# carrier_card.net
KiCad netlist of a schematic drawn in Altium Designer
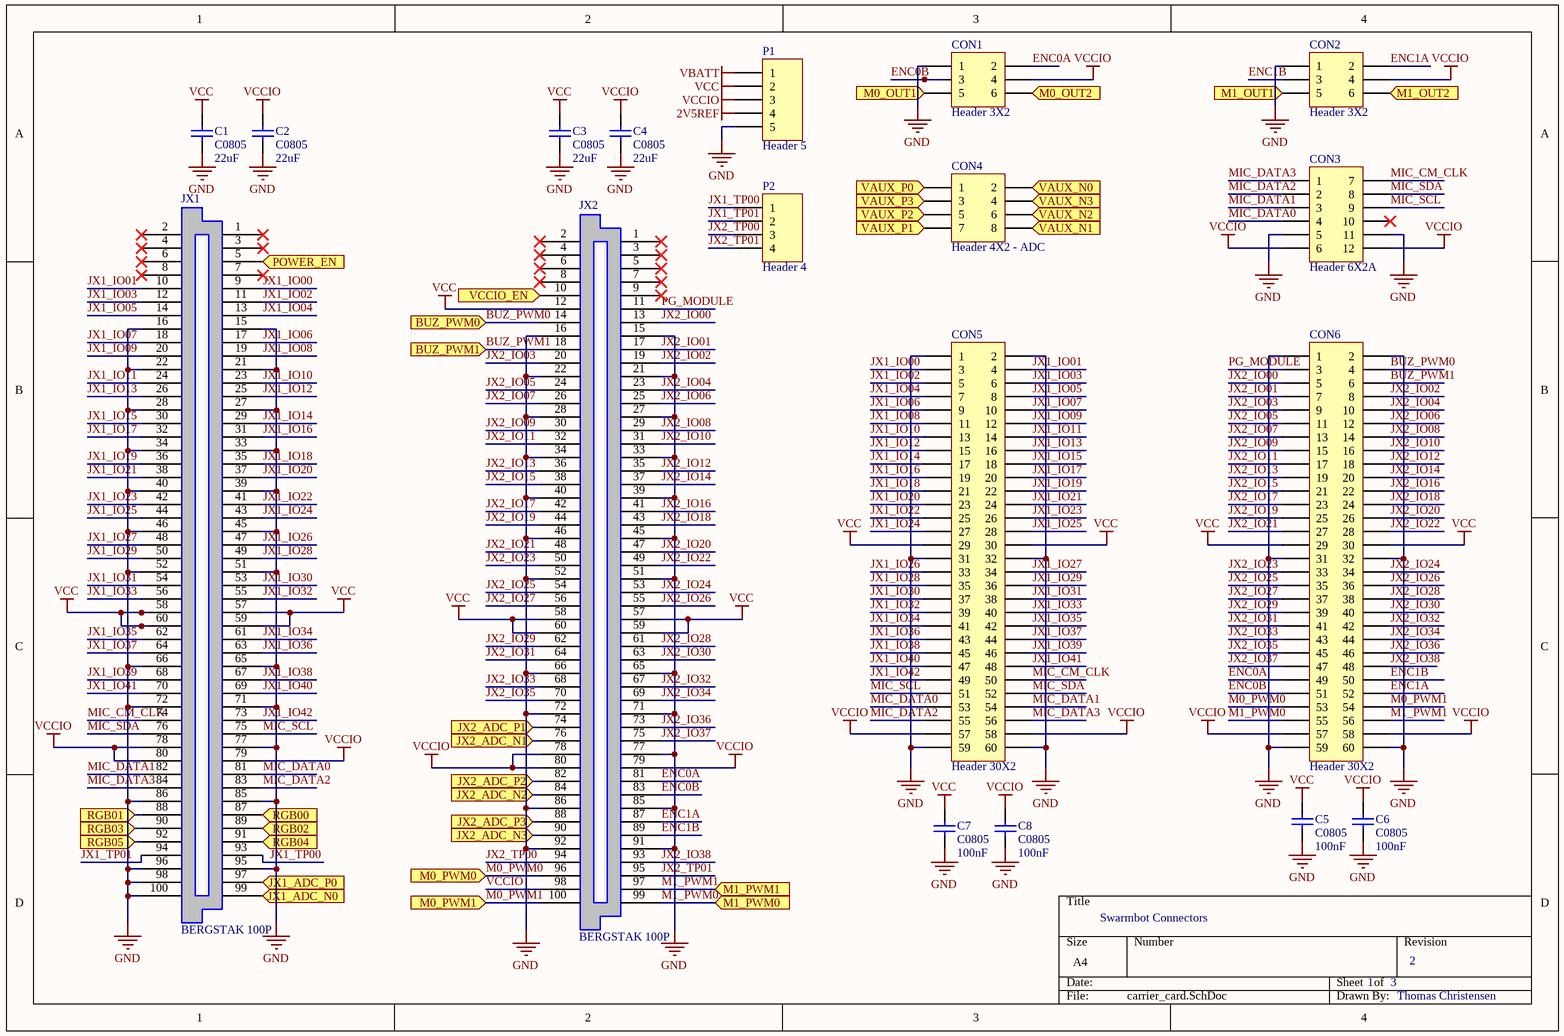
[diagram p0: carrier_card.SchDoc]

(export (version "E")
  (design (tool "Eeschema 10.0.6"))
  (components
    (comp (ref "C1")
      (value "C0805")
      (footprint "0805")
      (description "Ceramic Chip Capacitor - Standard")
      (fields (field (name "ALTIUM_VALUE") "22uF") (field (name "PUBLISHER") "Altium Limited"))
      (libsource (lib "KEMET Chip Capacitor") (part "C0805"))
    )
    (comp (ref "C2")
      (value "C0805")
      (footprint "0805")
      (description "Ceramic Chip Capacitor - Standard")
      (fields (field (name "ALTIUM_VALUE") "22uF") (field (name "PUBLISHER") "Altium Limited"))
      (libsource (lib "KEMET Chip Capacitor") (part "C0805"))
    )
    (comp (ref "C3")
      (value "C0805")
      (footprint "0805")
      (description "Ceramic Chip Capacitor - Standard")
      (fields (field (name "ALTIUM_VALUE") "22uF") (field (name "PUBLISHER") "Altium Limited"))
      (libsource (lib "KEMET Chip Capacitor") (part "C0805"))
    )
    (comp (ref "C4")
      (value "C0805")
      (footprint "0805")
      (description "Ceramic Chip Capacitor - Standard")
      (fields (field (name "ALTIUM_VALUE") "22uF") (field (name "PUBLISHER") "Altium Limited"))
      (libsource (lib "KEMET Chip Capacitor") (part "C0805"))
    )
    (comp (ref "C5")
      (value "C0805")
      (footprint "0805")
      (description "Ceramic Chip Capacitor - Standard")
      (fields (field (name "ALTIUM_VALUE") "100nF") (field (name "PUBLISHER") "Altium Limited"))
      (libsource (lib "KEMET Chip Capacitor") (part "C0805"))
    )
    (comp (ref "C6")
      (value "C0805")
      (footprint "0805")
      (description "Ceramic Chip Capacitor - Standard")
      (fields (field (name "ALTIUM_VALUE") "100nF") (field (name "PUBLISHER") "Altium Limited"))
      (libsource (lib "KEMET Chip Capacitor") (part "C0805"))
    )
    (comp (ref "C7")
      (value "C0805")
      (footprint "0805")
      (description "Ceramic Chip Capacitor - Standard")
      (fields (field (name "ALTIUM_VALUE") "100nF") (field (name "PUBLISHER") "Altium Limited"))
      (libsource (lib "KEMET Chip Capacitor") (part "C0805"))
    )
    (comp (ref "C8")
      (value "C0805")
      (footprint "0805")
      (description "Ceramic Chip Capacitor - Standard")
      (fields (field (name "ALTIUM_VALUE") "100nF") (field (name "PUBLISHER") "Altium Limited"))
      (libsource (lib "KEMET Chip Capacitor") (part "C0805"))
    )
    (comp (ref "CON1")
      (value "Header 3X2")
      (footprint "HDR2X3")
      (description "Header, 3-Pin, Dual row")
      (fields (field (name "PUBLISHER") "Altium Limited"))
      (libsource (lib "Miscellaneous Connectors") (part "Header 3X2"))
    )
    (comp (ref "CON2")
      (value "Header 3X2")
      (footprint "HDR2X3")
      (description "Header, 3-Pin, Dual row")
      (fields (field (name "PUBLISHER") "Altium Limited"))
      (libsource (lib "Miscellaneous Connectors") (part "Header 3X2"))
    )
    (comp (ref "CON3")
      (value "Header 6X2A")
      (footprint "HDR2X6_CEN")
      (description "Header, 6-Pin, Dual row")
      (fields (field (name "PUBLISHER") "Altium Limited"))
      (libsource (lib "Miscellaneous Connectors") (part "Header 6X2A"))
    )
    (comp (ref "CON4")
      (value "Header 4X2 - ADC")
      (footprint "HDR2X4")
      (description "Header, 4-Pin, Dual row")
      (fields (field (name "PUBLISHER") "Altium Limited"))
      (libsource (lib "Miscellaneous Connectors") (part "Header 4X2"))
    )
    (comp (ref "CON5")
      (value "Header 30X2")
      (footprint "HDR2X30")
      (description "Header, 30-Pin, Dual row")
      (fields (field (name "PUBLISHER") "Altium Limited"))
      (libsource (lib "Miscellaneous Connectors") (part "Header 30X2"))
    )
    (comp (ref "CON6")
      (value "Header 30X2")
      (footprint "HDR2X30")
      (description "Header, 30-Pin, Dual row")
      (fields (field (name "PUBLISHER") "Altium Limited"))
      (libsource (lib "Miscellaneous Connectors") (part "Header 30X2"))
    )
    (comp (ref "JX1")
      (value "BERGSTAK 100P")
      (footprint "swarmbot_pcblib:FCI_BERGSTAK_100P")
      (description "100p connector, BERGSTAK")
      (libsource (lib "swarmbot_schematic_library") (part "BERGSTAK 100P"))
    )
    (comp (ref "JX2")
      (value "BERGSTAK 100P")
      (footprint "swarmbot_pcblib:FCI_BERGSTAK_100P")
      (description "100p connector, BERGSTAK")
      (libsource (lib "swarmbot_schematic_library") (part "BERGSTAK 100P"))
    )
    (comp (ref "P1")
      (value "Header 5")
      (footprint "HDR1X5")
      (description "Header, 5-Pin")
      (fields (field (name "PUBLISHER") "Altium Limited"))
      (libsource (lib "Miscellaneous Connectors") (part "Header 5"))
    )
    (comp (ref "P2")
      (value "Header 4")
      (footprint "HDR1X4")
      (description "Header, 4-Pin")
      (fields (field (name "PUBLISHER") "Altium Limited"))
      (libsource (lib "Miscellaneous Connectors") (part "Header 4"))
    )
  )
  (nets
    (net (code "1") (name "/BUZ_PWM0") (class "Default")
      (node (ref "CON6") (pin "4") (pinfunction "4_4") (pintype "passive"))
      (node (ref "JX2") (pin "14") (pinfunction "14_14") (pintype "passive"))
    )
    (net (code "2") (name "/BUZ_PWM1") (class "Default")
      (node (ref "CON6") (pin "6") (pinfunction "6_6") (pintype "passive"))
      (node (ref "JX2") (pin "18") (pinfunction "18_18") (pintype "passive"))
    )
    (net (code "3") (name "/ENC0A") (class "Default")
      (node (ref "CON1") (pin "2") (pinfunction "2_2") (pintype "passive"))
      (node (ref "CON6") (pin "49") (pinfunction "49_49") (pintype "passive"))
      (node (ref "JX2") (pin "81") (pinfunction "81_81") (pintype "passive"))
    )
    (net (code "4") (name "/ENC0B") (class "Default")
      (node (ref "CON1") (pin "3") (pinfunction "3_3") (pintype "passive"))
      (node (ref "CON6") (pin "51") (pinfunction "51_51") (pintype "passive"))
      (node (ref "JX2") (pin "83") (pinfunction "83_83") (pintype "passive"))
    )
    (net (code "5") (name "/ENC1A") (class "Default")
      (node (ref "CON2") (pin "2") (pinfunction "2_2") (pintype "passive"))
      (node (ref "CON6") (pin "52") (pinfunction "52_52") (pintype "passive"))
      (node (ref "JX2") (pin "87") (pinfunction "87_87") (pintype "passive"))
    )
    (net (code "6") (name "/ENC1B") (class "Default")
      (node (ref "CON2") (pin "3") (pinfunction "3_3") (pintype "passive"))
      (node (ref "CON6") (pin "50") (pinfunction "50_50") (pintype "passive"))
      (node (ref "JX2") (pin "89") (pinfunction "89_89") (pintype "passive"))
    )
    (net (code "7") (name "/JX1_ADC_N0") (class "Default")
      (node (ref "JX1") (pin "99") (pinfunction "99_99") (pintype "passive"))
    )
    (net (code "8") (name "/JX1_ADC_P0") (class "Default")
      (node (ref "JX1") (pin "97") (pinfunction "97_97") (pintype "passive"))
    )
    (net (code "9") (name "/JX1_IO00") (class "Default")
      (node (ref "CON5") (pin "3") (pinfunction "3_3") (pintype "passive"))
      (node (ref "JX1") (pin "9") (pinfunction "9_9") (pintype "passive"))
    )
    (net (code "10") (name "/JX1_IO01") (class "Default")
      (node (ref "CON5") (pin "4") (pinfunction "4_4") (pintype "passive"))
      (node (ref "JX1") (pin "10") (pinfunction "10_10") (pintype "passive"))
    )
    (net (code "11") (name "/JX1_IO02") (class "Default")
      (node (ref "CON5") (pin "5") (pinfunction "5_5") (pintype "passive"))
      (node (ref "JX1") (pin "11") (pinfunction "11_11") (pintype "passive"))
    )
    (net (code "12") (name "/JX1_IO03") (class "Default")
      (node (ref "CON5") (pin "6") (pinfunction "6_6") (pintype "passive"))
      (node (ref "JX1") (pin "12") (pinfunction "12_12") (pintype "passive"))
    )
    (net (code "13") (name "/JX1_IO04") (class "Default")
      (node (ref "CON5") (pin "7") (pinfunction "7_7") (pintype "passive"))
      (node (ref "JX1") (pin "13") (pinfunction "13_13") (pintype "passive"))
    )
    (net (code "14") (name "/JX1_IO05") (class "Default")
      (node (ref "CON5") (pin "8") (pinfunction "8_8") (pintype "passive"))
      (node (ref "JX1") (pin "14") (pinfunction "14_14") (pintype "passive"))
    )
    (net (code "15") (name "/JX1_IO06") (class "Default")
      (node (ref "CON5") (pin "9") (pinfunction "9_9") (pintype "passive"))
      (node (ref "JX1") (pin "17") (pinfunction "17_17") (pintype "passive"))
    )
    (net (code "16") (name "/JX1_IO07") (class "Default")
      (node (ref "CON5") (pin "10") (pinfunction "10_10") (pintype "passive"))
      (node (ref "JX1") (pin "18") (pinfunction "18_18") (pintype "passive"))
    )
    (net (code "17") (name "/JX1_IO08") (class "Default")
      (node (ref "CON5") (pin "11") (pinfunction "11_11") (pintype "passive"))
      (node (ref "JX1") (pin "19") (pinfunction "19_19") (pintype "passive"))
    )
    (net (code "18") (name "/JX1_IO09") (class "Default")
      (node (ref "CON5") (pin "12") (pinfunction "12_12") (pintype "passive"))
      (node (ref "JX1") (pin "20") (pinfunction "20_20") (pintype "passive"))
    )
    (net (code "19") (name "/JX1_IO10") (class "Default")
      (node (ref "CON5") (pin "13") (pinfunction "13_13") (pintype "passive"))
      (node (ref "JX1") (pin "23") (pinfunction "23_23") (pintype "passive"))
    )
    (net (code "20") (name "/JX1_IO11") (class "Default")
      (node (ref "CON5") (pin "14") (pinfunction "14_14") (pintype "passive"))
      (node (ref "JX1") (pin "24") (pinfunction "24_24") (pintype "passive"))
    )
    (net (code "21") (name "/JX1_IO12") (class "Default")
      (node (ref "CON5") (pin "15") (pinfunction "15_15") (pintype "passive"))
      (node (ref "JX1") (pin "25") (pinfunction "25_25") (pintype "passive"))
    )
    (net (code "22") (name "/JX1_IO13") (class "Default")
      (node (ref "CON5") (pin "16") (pinfunction "16_16") (pintype "passive"))
      (node (ref "JX1") (pin "26") (pinfunction "26_26") (pintype "passive"))
    )
    (net (code "23") (name "/JX1_IO14") (class "Default")
      (node (ref "CON5") (pin "17") (pinfunction "17_17") (pintype "passive"))
      (node (ref "JX1") (pin "29") (pinfunction "29_29") (pintype "passive"))
    )
    (net (code "24") (name "/JX1_IO15") (class "Default")
      (node (ref "CON5") (pin "18") (pinfunction "18_18") (pintype "passive"))
      (node (ref "JX1") (pin "30") (pinfunction "30_30") (pintype "passive"))
    )
    (net (code "25") (name "/JX1_IO16") (class "Default")
      (node (ref "CON5") (pin "19") (pinfunction "19_19") (pintype "passive"))
      (node (ref "JX1") (pin "31") (pinfunction "31_31") (pintype "passive"))
    )
    (net (code "26") (name "/JX1_IO17") (class "Default")
      (node (ref "CON5") (pin "20") (pinfunction "20_20") (pintype "passive"))
      (node (ref "JX1") (pin "32") (pinfunction "32_32") (pintype "passive"))
    )
    (net (code "27") (name "/JX1_IO18") (class "Default")
      (node (ref "CON5") (pin "21") (pinfunction "21_21") (pintype "passive"))
      (node (ref "JX1") (pin "35") (pinfunction "35_35") (pintype "passive"))
    )
    (net (code "28") (name "/JX1_IO19") (class "Default")
      (node (ref "CON5") (pin "22") (pinfunction "22_22") (pintype "passive"))
      (node (ref "JX1") (pin "36") (pinfunction "36_36") (pintype "passive"))
    )
    (net (code "29") (name "/JX1_IO20") (class "Default")
      (node (ref "CON5") (pin "23") (pinfunction "23_23") (pintype "passive"))
      (node (ref "JX1") (pin "37") (pinfunction "37_37") (pintype "passive"))
    )
    (net (code "30") (name "/JX1_IO21") (class "Default")
      (node (ref "CON5") (pin "24") (pinfunction "24_24") (pintype "passive"))
      (node (ref "JX1") (pin "38") (pinfunction "38_38") (pintype "passive"))
    )
    (net (code "31") (name "/JX1_IO22") (class "Default")
      (node (ref "CON5") (pin "25") (pinfunction "25_25") (pintype "passive"))
      (node (ref "JX1") (pin "41") (pinfunction "41_41") (pintype "passive"))
    )
    (net (code "32") (name "/JX1_IO23") (class "Default")
      (node (ref "CON5") (pin "26") (pinfunction "26_26") (pintype "passive"))
      (node (ref "JX1") (pin "42") (pinfunction "42_42") (pintype "passive"))
    )
    (net (code "33") (name "/JX1_IO24") (class "Default")
      (node (ref "CON5") (pin "27") (pinfunction "27_27") (pintype "passive"))
      (node (ref "JX1") (pin "43") (pinfunction "43_43") (pintype "passive"))
    )
    (net (code "34") (name "/JX1_IO25") (class "Default")
      (node (ref "CON5") (pin "28") (pinfunction "28_28") (pintype "passive"))
      (node (ref "JX1") (pin "44") (pinfunction "44_44") (pintype "passive"))
    )
    (net (code "35") (name "/JX1_IO26") (class "Default")
      (node (ref "CON5") (pin "33") (pinfunction "33_33") (pintype "passive"))
      (node (ref "JX1") (pin "47") (pinfunction "47_47") (pintype "passive"))
    )
    (net (code "36") (name "/JX1_IO27") (class "Default")
      (node (ref "CON5") (pin "34") (pinfunction "34_34") (pintype "passive"))
      (node (ref "JX1") (pin "48") (pinfunction "48_48") (pintype "passive"))
    )
    (net (code "37") (name "/JX1_IO28") (class "Default")
      (node (ref "CON5") (pin "35") (pinfunction "35_35") (pintype "passive"))
      (node (ref "JX1") (pin "49") (pinfunction "49_49") (pintype "passive"))
    )
    (net (code "38") (name "/JX1_IO29") (class "Default")
      (node (ref "CON5") (pin "36") (pinfunction "36_36") (pintype "passive"))
      (node (ref "JX1") (pin "50") (pinfunction "50_50") (pintype "passive"))
    )
    (net (code "39") (name "/JX1_IO30") (class "Default")
      (node (ref "CON5") (pin "37") (pinfunction "37_37") (pintype "passive"))
      (node (ref "JX1") (pin "53") (pinfunction "53_53") (pintype "passive"))
    )
    (net (code "40") (name "/JX1_IO31") (class "Default")
      (node (ref "CON5") (pin "38") (pinfunction "38_38") (pintype "passive"))
      (node (ref "JX1") (pin "54") (pinfunction "54_54") (pintype "passive"))
    )
    (net (code "41") (name "/JX1_IO32") (class "Default")
      (node (ref "CON5") (pin "39") (pinfunction "39_39") (pintype "passive"))
      (node (ref "JX1") (pin "55") (pinfunction "55_55") (pintype "passive"))
    )
    (net (code "42") (name "/JX1_IO33") (class "Default")
      (node (ref "CON5") (pin "40") (pinfunction "40_40") (pintype "passive"))
      (node (ref "JX1") (pin "56") (pinfunction "56_56") (pintype "passive"))
    )
    (net (code "43") (name "/JX1_IO34") (class "Default")
      (node (ref "CON5") (pin "41") (pinfunction "41_41") (pintype "passive"))
      (node (ref "JX1") (pin "61") (pinfunction "61_61") (pintype "passive"))
    )
    (net (code "44") (name "/JX1_IO35") (class "Default")
      (node (ref "CON5") (pin "42") (pinfunction "42_42") (pintype "passive"))
      (node (ref "JX1") (pin "62") (pinfunction "62_62") (pintype "passive"))
    )
    (net (code "45") (name "/JX1_IO36") (class "Default")
      (node (ref "CON5") (pin "43") (pinfunction "43_43") (pintype "passive"))
      (node (ref "JX1") (pin "63") (pinfunction "63_63") (pintype "passive"))
    )
    (net (code "46") (name "/JX1_IO37") (class "Default")
      (node (ref "CON5") (pin "44") (pinfunction "44_44") (pintype "passive"))
      (node (ref "JX1") (pin "64") (pinfunction "64_64") (pintype "passive"))
    )
    (net (code "47") (name "/JX1_IO38") (class "Default")
      (node (ref "CON5") (pin "45") (pinfunction "45_45") (pintype "passive"))
      (node (ref "JX1") (pin "67") (pinfunction "67_67") (pintype "passive"))
    )
    (net (code "48") (name "/JX1_IO39") (class "Default")
      (node (ref "CON5") (pin "46") (pinfunction "46_46") (pintype "passive"))
      (node (ref "JX1") (pin "68") (pinfunction "68_68") (pintype "passive"))
    )
    (net (code "49") (name "/JX1_IO40") (class "Default")
      (node (ref "CON5") (pin "47") (pinfunction "47_47") (pintype "passive"))
      (node (ref "JX1") (pin "69") (pinfunction "69_69") (pintype "passive"))
    )
    (net (code "50") (name "/JX1_IO41") (class "Default")
      (node (ref "CON5") (pin "48") (pinfunction "48_48") (pintype "passive"))
      (node (ref "JX1") (pin "70") (pinfunction "70_70") (pintype "passive"))
    )
    (net (code "51") (name "/JX1_IO42") (class "Default")
      (node (ref "CON5") (pin "49") (pinfunction "49_49") (pintype "passive"))
      (node (ref "JX1") (pin "73") (pinfunction "73_73") (pintype "passive"))
    )
    (net (code "52") (name "/JX1_TP00") (class "Default")
      (node (ref "JX1") (pin "93") (pinfunction "93_93") (pintype "passive"))
      (node (ref "P2") (pin "1") (pinfunction "1_1") (pintype "passive"))
    )
    (net (code "53") (name "/JX1_TP01") (class "Default")
      (node (ref "JX1") (pin "94") (pinfunction "94_94") (pintype "passive"))
      (node (ref "P2") (pin "2") (pinfunction "2_2") (pintype "passive"))
    )
    (net (code "54") (name "/JX2_ADC_N1") (class "Default")
      (node (ref "JX2") (pin "76") (pinfunction "76_76") (pintype "passive"))
    )
    (net (code "55") (name "/JX2_ADC_N2") (class "Default")
      (node (ref "JX2") (pin "84") (pinfunction "84_84") (pintype "passive"))
    )
    (net (code "56") (name "/JX2_ADC_N3") (class "Default")
      (node (ref "JX2") (pin "90") (pinfunction "90_90") (pintype "passive"))
    )
    (net (code "57") (name "/JX2_ADC_P1") (class "Default")
      (node (ref "JX2") (pin "74") (pinfunction "74_74") (pintype "passive"))
    )
    (net (code "58") (name "/JX2_ADC_P2") (class "Default")
      (node (ref "JX2") (pin "82") (pinfunction "82_82") (pintype "passive"))
    )
    (net (code "59") (name "/JX2_ADC_P3") (class "Default")
      (node (ref "JX2") (pin "88") (pinfunction "88_88") (pintype "passive"))
    )
    (net (code "60") (name "/JX2_IO00") (class "Default")
      (node (ref "CON6") (pin "5") (pinfunction "5_5") (pintype "passive"))
      (node (ref "JX2") (pin "13") (pinfunction "13_13") (pintype "passive"))
    )
    (net (code "61") (name "/JX2_IO01") (class "Default")
      (node (ref "CON6") (pin "7") (pinfunction "7_7") (pintype "passive"))
      (node (ref "JX2") (pin "17") (pinfunction "17_17") (pintype "passive"))
    )
    (net (code "62") (name "/JX2_IO02") (class "Default")
      (node (ref "CON6") (pin "8") (pinfunction "8_8") (pintype "passive"))
      (node (ref "JX2") (pin "19") (pinfunction "19_19") (pintype "passive"))
    )
    (net (code "63") (name "/JX2_IO03") (class "Default")
      (node (ref "CON6") (pin "9") (pinfunction "9_9") (pintype "passive"))
      (node (ref "JX2") (pin "20") (pinfunction "20_20") (pintype "passive"))
    )
    (net (code "64") (name "/JX2_IO04") (class "Default")
      (node (ref "CON6") (pin "10") (pinfunction "10_10") (pintype "passive"))
      (node (ref "JX2") (pin "23") (pinfunction "23_23") (pintype "passive"))
    )
    (net (code "65") (name "/JX2_IO05") (class "Default")
      (node (ref "CON6") (pin "11") (pinfunction "11_11") (pintype "passive"))
      (node (ref "JX2") (pin "24") (pinfunction "24_24") (pintype "passive"))
    )
    (net (code "66") (name "/JX2_IO06") (class "Default")
      (node (ref "CON6") (pin "12") (pinfunction "12_12") (pintype "passive"))
      (node (ref "JX2") (pin "25") (pinfunction "25_25") (pintype "passive"))
    )
    (net (code "67") (name "/JX2_IO07") (class "Default")
      (node (ref "CON6") (pin "13") (pinfunction "13_13") (pintype "passive"))
      (node (ref "JX2") (pin "26") (pinfunction "26_26") (pintype "passive"))
    )
    (net (code "68") (name "/JX2_IO08") (class "Default")
      (node (ref "CON6") (pin "14") (pinfunction "14_14") (pintype "passive"))
      (node (ref "JX2") (pin "29") (pinfunction "29_29") (pintype "passive"))
    )
    (net (code "69") (name "/JX2_IO09") (class "Default")
      (node (ref "CON6") (pin "15") (pinfunction "15_15") (pintype "passive"))
      (node (ref "JX2") (pin "30") (pinfunction "30_30") (pintype "passive"))
    )
    (net (code "70") (name "/JX2_IO10") (class "Default")
      (node (ref "CON6") (pin "16") (pinfunction "16_16") (pintype "passive"))
      (node (ref "JX2") (pin "31") (pinfunction "31_31") (pintype "passive"))
    )
    (net (code "71") (name "/JX2_IO11") (class "Default")
      (node (ref "CON6") (pin "17") (pinfunction "17_17") (pintype "passive"))
      (node (ref "JX2") (pin "32") (pinfunction "32_32") (pintype "passive"))
    )
    (net (code "72") (name "/JX2_IO12") (class "Default")
      (node (ref "CON6") (pin "18") (pinfunction "18_18") (pintype "passive"))
      (node (ref "JX2") (pin "35") (pinfunction "35_35") (pintype "passive"))
    )
    (net (code "73") (name "/JX2_IO13") (class "Default")
      (node (ref "CON6") (pin "19") (pinfunction "19_19") (pintype "passive"))
      (node (ref "JX2") (pin "36") (pinfunction "36_36") (pintype "passive"))
    )
    (net (code "74") (name "/JX2_IO14") (class "Default")
      (node (ref "CON6") (pin "20") (pinfunction "20_20") (pintype "passive"))
      (node (ref "JX2") (pin "37") (pinfunction "37_37") (pintype "passive"))
    )
    (net (code "75") (name "/JX2_IO15") (class "Default")
      (node (ref "CON6") (pin "21") (pinfunction "21_21") (pintype "passive"))
      (node (ref "JX2") (pin "38") (pinfunction "38_38") (pintype "passive"))
    )
    (net (code "76") (name "/JX2_IO16") (class "Default")
      (node (ref "CON6") (pin "22") (pinfunction "22_22") (pintype "passive"))
      (node (ref "JX2") (pin "41") (pinfunction "41_41") (pintype "passive"))
    )
    (net (code "77") (name "/JX2_IO17") (class "Default")
      (node (ref "CON6") (pin "23") (pinfunction "23_23") (pintype "passive"))
      (node (ref "JX2") (pin "42") (pinfunction "42_42") (pintype "passive"))
    )
    (net (code "78") (name "/JX2_IO18") (class "Default")
      (node (ref "CON6") (pin "24") (pinfunction "24_24") (pintype "passive"))
      (node (ref "JX2") (pin "43") (pinfunction "43_43") (pintype "passive"))
    )
    (net (code "79") (name "/JX2_IO19") (class "Default")
      (node (ref "CON6") (pin "25") (pinfunction "25_25") (pintype "passive"))
      (node (ref "JX2") (pin "44") (pinfunction "44_44") (pintype "passive"))
    )
    (net (code "80") (name "/JX2_IO20") (class "Default")
      (node (ref "CON6") (pin "26") (pinfunction "26_26") (pintype "passive"))
      (node (ref "JX2") (pin "47") (pinfunction "47_47") (pintype "passive"))
    )
    (net (code "81") (name "/JX2_IO21") (class "Default")
      (node (ref "CON6") (pin "27") (pinfunction "27_27") (pintype "passive"))
      (node (ref "JX2") (pin "48") (pinfunction "48_48") (pintype "passive"))
    )
    (net (code "82") (name "/JX2_IO22") (class "Default")
      (node (ref "CON6") (pin "28") (pinfunction "28_28") (pintype "passive"))
      (node (ref "JX2") (pin "49") (pinfunction "49_49") (pintype "passive"))
    )
    (net (code "83") (name "/JX2_IO23") (class "Default")
      (node (ref "CON6") (pin "33") (pinfunction "33_33") (pintype "passive"))
      (node (ref "JX2") (pin "50") (pinfunction "50_50") (pintype "passive"))
    )
    (net (code "84") (name "/JX2_IO24") (class "Default")
      (node (ref "CON6") (pin "34") (pinfunction "34_34") (pintype "passive"))
      (node (ref "JX2") (pin "53") (pinfunction "53_53") (pintype "passive"))
    )
    (net (code "85") (name "/JX2_IO25") (class "Default")
      (node (ref "CON6") (pin "35") (pinfunction "35_35") (pintype "passive"))
      (node (ref "JX2") (pin "54") (pinfunction "54_54") (pintype "passive"))
    )
    (net (code "86") (name "/JX2_IO26") (class "Default")
      (node (ref "CON6") (pin "36") (pinfunction "36_36") (pintype "passive"))
      (node (ref "JX2") (pin "55") (pinfunction "55_55") (pintype "passive"))
    )
    (net (code "87") (name "/JX2_IO27") (class "Default")
      (node (ref "CON6") (pin "37") (pinfunction "37_37") (pintype "passive"))
      (node (ref "JX2") (pin "56") (pinfunction "56_56") (pintype "passive"))
    )
    (net (code "88") (name "/JX2_IO28") (class "Default")
      (node (ref "CON6") (pin "38") (pinfunction "38_38") (pintype "passive"))
      (node (ref "JX2") (pin "61") (pinfunction "61_61") (pintype "passive"))
    )
    (net (code "89") (name "/JX2_IO29") (class "Default")
      (node (ref "CON6") (pin "39") (pinfunction "39_39") (pintype "passive"))
      (node (ref "JX2") (pin "62") (pinfunction "62_62") (pintype "passive"))
    )
    (net (code "90") (name "/JX2_IO30") (class "Default")
      (node (ref "CON6") (pin "40") (pinfunction "40_40") (pintype "passive"))
      (node (ref "JX2") (pin "63") (pinfunction "63_63") (pintype "passive"))
    )
    (net (code "91") (name "/JX2_IO31") (class "Default")
      (node (ref "CON6") (pin "41") (pinfunction "41_41") (pintype "passive"))
      (node (ref "JX2") (pin "64") (pinfunction "64_64") (pintype "passive"))
    )
    (net (code "92") (name "/JX2_IO32") (class "Default")
      (node (ref "CON6") (pin "42") (pinfunction "42_42") (pintype "passive"))
      (node (ref "JX2") (pin "67") (pinfunction "67_67") (pintype "passive"))
    )
    (net (code "93") (name "/JX2_IO33") (class "Default")
      (node (ref "CON6") (pin "43") (pinfunction "43_43") (pintype "passive"))
      (node (ref "JX2") (pin "68") (pinfunction "68_68") (pintype "passive"))
    )
    (net (code "94") (name "/JX2_IO34") (class "Default")
      (node (ref "CON6") (pin "44") (pinfunction "44_44") (pintype "passive"))
      (node (ref "JX2") (pin "69") (pinfunction "69_69") (pintype "passive"))
    )
    (net (code "95") (name "/JX2_IO35") (class "Default")
      (node (ref "CON6") (pin "45") (pinfunction "45_45") (pintype "passive"))
      (node (ref "JX2") (pin "70") (pinfunction "70_70") (pintype "passive"))
    )
    (net (code "96") (name "/JX2_IO36") (class "Default")
      (node (ref "CON6") (pin "46") (pinfunction "46_46") (pintype "passive"))
      (node (ref "JX2") (pin "73") (pinfunction "73_73") (pintype "passive"))
    )
    (net (code "97") (name "/JX2_IO37") (class "Default")
      (node (ref "CON6") (pin "47") (pinfunction "47_47") (pintype "passive"))
      (node (ref "JX2") (pin "75") (pinfunction "75_75") (pintype "passive"))
    )
    (net (code "98") (name "/JX2_IO38") (class "Default")
      (node (ref "CON6") (pin "48") (pinfunction "48_48") (pintype "passive"))
      (node (ref "JX2") (pin "93") (pinfunction "93_93") (pintype "passive"))
    )
    (net (code "99") (name "/JX2_TP00") (class "Default")
      (node (ref "JX2") (pin "94") (pinfunction "94_94") (pintype "passive"))
      (node (ref "P2") (pin "3") (pinfunction "3_3") (pintype "passive"))
    )
    (net (code "100") (name "/JX2_TP01") (class "Default")
      (node (ref "JX2") (pin "95") (pinfunction "95_95") (pintype "passive"))
      (node (ref "P2") (pin "4") (pinfunction "4_4") (pintype "passive"))
    )
    (net (code "101") (name "/M0_OUT1") (class "Default")
      (node (ref "CON1") (pin "5") (pinfunction "5_5") (pintype "passive"))
    )
    (net (code "102") (name "/M0_OUT2") (class "Default")
      (node (ref "CON1") (pin "6") (pinfunction "6_6") (pintype "passive"))
    )
    (net (code "103") (name "/M0_PWM0") (class "Default")
      (node (ref "CON6") (pin "53") (pinfunction "53_53") (pintype "passive"))
      (node (ref "JX2") (pin "96") (pinfunction "96_96") (pintype "passive"))
    )
    (net (code "104") (name "/M0_PWM1") (class "Default")
      (node (ref "CON6") (pin "54") (pinfunction "54_54") (pintype "passive"))
      (node (ref "JX2") (pin "100") (pinfunction "100_100") (pintype "passive"))
    )
    (net (code "105") (name "/M1_OUT1") (class "Default")
      (node (ref "CON2") (pin "5") (pinfunction "5_5") (pintype "passive"))
    )
    (net (code "106") (name "/M1_OUT2") (class "Default")
      (node (ref "CON2") (pin "6") (pinfunction "6_6") (pintype "passive"))
    )
    (net (code "107") (name "/M1_PWM0") (class "Default")
      (node (ref "CON6") (pin "55") (pinfunction "55_55") (pintype "passive"))
      (node (ref "JX2") (pin "99") (pinfunction "99_99") (pintype "passive"))
    )
    (net (code "108") (name "/M1_PWM1") (class "Default")
      (node (ref "CON6") (pin "56") (pinfunction "56_56") (pintype "passive"))
      (node (ref "JX2") (pin "97") (pinfunction "97_97") (pintype "passive"))
    )
    (net (code "109") (name "/MIC_CM_CLK") (class "Default")
      (node (ref "CON3") (pin "7") (pinfunction "7_7") (pintype "passive"))
      (node (ref "CON5") (pin "50") (pinfunction "50_50") (pintype "passive"))
      (node (ref "JX1") (pin "74") (pinfunction "74_74") (pintype "passive"))
    )
    (net (code "110") (name "/MIC_DATA0") (class "Default")
      (node (ref "CON3") (pin "4") (pinfunction "4_4") (pintype "passive"))
      (node (ref "CON5") (pin "53") (pinfunction "53_53") (pintype "passive"))
      (node (ref "JX1") (pin "81") (pinfunction "81_81") (pintype "passive"))
    )
    (net (code "111") (name "/MIC_DATA1") (class "Default")
      (node (ref "CON3") (pin "3") (pinfunction "3_3") (pintype "passive"))
      (node (ref "CON5") (pin "54") (pinfunction "54_54") (pintype "passive"))
      (node (ref "JX1") (pin "82") (pinfunction "82_82") (pintype "passive"))
    )
    (net (code "112") (name "/MIC_DATA2") (class "Default")
      (node (ref "CON3") (pin "2") (pinfunction "2_2") (pintype "passive"))
      (node (ref "CON5") (pin "55") (pinfunction "55_55") (pintype "passive"))
      (node (ref "JX1") (pin "83") (pinfunction "83_83") (pintype "passive"))
    )
    (net (code "113") (name "/MIC_DATA3") (class "Default")
      (node (ref "CON3") (pin "1") (pinfunction "1_1") (pintype "passive"))
      (node (ref "CON5") (pin "56") (pinfunction "56_56") (pintype "passive"))
      (node (ref "JX1") (pin "84") (pinfunction "84_84") (pintype "passive"))
    )
    (net (code "114") (name "/MIC_SCL") (class "Default")
      (node (ref "CON3") (pin "9") (pinfunction "9_9") (pintype "passive"))
      (node (ref "CON5") (pin "51") (pinfunction "51_51") (pintype "passive"))
      (node (ref "JX1") (pin "75") (pinfunction "75_75") (pintype "passive"))
    )
    (net (code "115") (name "/MIC_SDA") (class "Default")
      (node (ref "CON3") (pin "8") (pinfunction "8_8") (pintype "passive"))
      (node (ref "CON5") (pin "52") (pinfunction "52_52") (pintype "passive"))
      (node (ref "JX1") (pin "76") (pinfunction "76_76") (pintype "passive"))
    )
    (net (code "116") (name "/PG_MODULE") (class "Default")
      (node (ref "CON6") (pin "3") (pinfunction "3_3") (pintype "passive"))
      (node (ref "JX2") (pin "11") (pinfunction "11_11") (pintype "passive"))
    )
    (net (code "117") (name "/POWER_EN") (class "Default")
      (node (ref "JX1") (pin "5") (pinfunction "5_5") (pintype "passive"))
    )
    (net (code "118") (name "/RGB00") (class "Default")
      (node (ref "JX1") (pin "87") (pinfunction "87_87") (pintype "passive"))
    )
    (net (code "119") (name "/RGB01") (class "Default")
      (node (ref "JX1") (pin "88") (pinfunction "88_88") (pintype "passive"))
    )
    (net (code "120") (name "/RGB02") (class "Default")
      (node (ref "JX1") (pin "89") (pinfunction "89_89") (pintype "passive"))
    )
    (net (code "121") (name "/RGB03") (class "Default")
      (node (ref "JX1") (pin "90") (pinfunction "90_90") (pintype "passive"))
    )
    (net (code "122") (name "/RGB04") (class "Default")
      (node (ref "JX1") (pin "91") (pinfunction "91_91") (pintype "passive"))
    )
    (net (code "123") (name "/RGB05") (class "Default")
      (node (ref "JX1") (pin "92") (pinfunction "92_92") (pintype "passive"))
    )
    (net (code "124") (name "/VAUX_N0") (class "Default")
      (node (ref "CON4") (pin "2") (pinfunction "2_2") (pintype "passive"))
    )
    (net (code "125") (name "/VAUX_N1") (class "Default")
      (node (ref "CON4") (pin "8") (pinfunction "8_8") (pintype "passive"))
    )
    (net (code "126") (name "/VAUX_N2") (class "Default")
      (node (ref "CON4") (pin "6") (pinfunction "6_6") (pintype "passive"))
    )
    (net (code "127") (name "/VAUX_N3") (class "Default")
      (node (ref "CON4") (pin "4") (pinfunction "4_4") (pintype "passive"))
    )
    (net (code "128") (name "/VAUX_P0") (class "Default")
      (node (ref "CON4") (pin "1") (pinfunction "1_1") (pintype "passive"))
    )
    (net (code "129") (name "/VAUX_P1") (class "Default")
      (node (ref "CON4") (pin "7") (pinfunction "7_7") (pintype "passive"))
    )
    (net (code "130") (name "/VAUX_P2") (class "Default")
      (node (ref "CON4") (pin "5") (pinfunction "5_5") (pintype "passive"))
    )
    (net (code "131") (name "/VAUX_P3") (class "Default")
      (node (ref "CON4") (pin "3") (pinfunction "3_3") (pintype "passive"))
    )
    (net (code "132") (name "/VCCIO_EN") (class "Default")
      (node (ref "JX2") (pin "10") (pinfunction "10_10") (pintype "passive"))
    )
    (net (code "133") (name "2V5REF") (class "Default")
      (node (ref "P1") (pin "4") (pinfunction "4_4") (pintype "passive"))
    )
    (net (code "134") (name "GND") (class "Default")
      (node (ref "C1") (pin "1") (pinfunction "1_1") (pintype "passive"))
      (node (ref "C2") (pin "1") (pinfunction "1_1") (pintype "passive"))
      (node (ref "C3") (pin "1") (pinfunction "1_1") (pintype "passive"))
      (node (ref "C4") (pin "1") (pinfunction "1_1") (pintype "passive"))
      (node (ref "C5") (pin "1") (pinfunction "1_1") (pintype "passive"))
      (node (ref "C6") (pin "1") (pinfunction "1_1") (pintype "passive"))
      (node (ref "C7") (pin "1") (pinfunction "1_1") (pintype "passive"))
      (node (ref "C8") (pin "1") (pinfunction "1_1") (pintype "passive"))
      (node (ref "CON1") (pin "1") (pinfunction "1_1") (pintype "passive"))
      (node (ref "CON2") (pin "1") (pinfunction "1_1") (pintype "passive"))
      (node (ref "CON3") (pin "11") (pinfunction "11_11") (pintype "passive"))
      (node (ref "CON3") (pin "5") (pinfunction "5_5") (pintype "passive"))
      (node (ref "CON5") (pin "1") (pinfunction "1_1") (pintype "passive"))
      (node (ref "CON5") (pin "2") (pinfunction "2_2") (pintype "passive"))
      (node (ref "CON5") (pin "31") (pinfunction "31_31") (pintype "passive"))
      (node (ref "CON5") (pin "32") (pinfunction "32_32") (pintype "passive"))
      (node (ref "CON5") (pin "59") (pinfunction "59_59") (pintype "passive"))
      (node (ref "CON5") (pin "60") (pinfunction "60_60") (pintype "passive"))
      (node (ref "CON6") (pin "1") (pinfunction "1_1") (pintype "passive"))
      (node (ref "CON6") (pin "2") (pinfunction "2_2") (pintype "passive"))
      (node (ref "CON6") (pin "31") (pinfunction "31_31") (pintype "passive"))
      (node (ref "CON6") (pin "32") (pinfunction "32_32") (pintype "passive"))
      (node (ref "CON6") (pin "59") (pinfunction "59_59") (pintype "passive"))
      (node (ref "CON6") (pin "60") (pinfunction "60_60") (pintype "passive"))
      (node (ref "JX1") (pin "100") (pinfunction "100_100") (pintype "passive"))
      (node (ref "JX1") (pin "15") (pinfunction "15_15") (pintype "passive"))
      (node (ref "JX1") (pin "16") (pinfunction "16_16") (pintype "passive"))
      (node (ref "JX1") (pin "21") (pinfunction "21_21") (pintype "passive"))
      (node (ref "JX1") (pin "22") (pinfunction "22_22") (pintype "passive"))
      (node (ref "JX1") (pin "27") (pinfunction "27_27") (pintype "passive"))
      (node (ref "JX1") (pin "28") (pinfunction "28_28") (pintype "passive"))
      (node (ref "JX1") (pin "33") (pinfunction "33_33") (pintype "passive"))
      (node (ref "JX1") (pin "34") (pinfunction "34_34") (pintype "passive"))
      (node (ref "JX1") (pin "39") (pinfunction "39_39") (pintype "passive"))
      (node (ref "JX1") (pin "40") (pinfunction "40_40") (pintype "passive"))
      (node (ref "JX1") (pin "45") (pinfunction "45_45") (pintype "passive"))
      (node (ref "JX1") (pin "46") (pinfunction "46_46") (pintype "passive"))
      (node (ref "JX1") (pin "51") (pinfunction "51_51") (pintype "passive"))
      (node (ref "JX1") (pin "52") (pinfunction "52_52") (pintype "passive"))
      (node (ref "JX1") (pin "65") (pinfunction "65_65") (pintype "passive"))
      (node (ref "JX1") (pin "66") (pinfunction "66_66") (pintype "passive"))
      (node (ref "JX1") (pin "71") (pinfunction "71_71") (pintype "passive"))
      (node (ref "JX1") (pin "72") (pinfunction "72_72") (pintype "passive"))
      (node (ref "JX1") (pin "77") (pinfunction "77_77") (pintype "passive"))
      (node (ref "JX1") (pin "85") (pinfunction "85_85") (pintype "passive"))
      (node (ref "JX1") (pin "86") (pinfunction "86_86") (pintype "passive"))
      (node (ref "JX1") (pin "95") (pinfunction "95_95") (pintype "passive"))
      (node (ref "JX1") (pin "96") (pinfunction "96_96") (pintype "passive"))
      (node (ref "JX1") (pin "98") (pinfunction "98_98") (pintype "passive"))
      (node (ref "JX2") (pin "15") (pinfunction "15_15") (pintype "passive"))
      (node (ref "JX2") (pin "16") (pinfunction "16_16") (pintype "passive"))
      (node (ref "JX2") (pin "21") (pinfunction "21_21") (pintype "passive"))
      (node (ref "JX2") (pin "22") (pinfunction "22_22") (pintype "passive"))
      (node (ref "JX2") (pin "27") (pinfunction "27_27") (pintype "passive"))
      (node (ref "JX2") (pin "28") (pinfunction "28_28") (pintype "passive"))
      (node (ref "JX2") (pin "33") (pinfunction "33_33") (pintype "passive"))
      (node (ref "JX2") (pin "34") (pinfunction "34_34") (pintype "passive"))
      (node (ref "JX2") (pin "39") (pinfunction "39_39") (pintype "passive"))
      (node (ref "JX2") (pin "40") (pinfunction "40_40") (pintype "passive"))
      (node (ref "JX2") (pin "45") (pinfunction "45_45") (pintype "passive"))
      (node (ref "JX2") (pin "46") (pinfunction "46_46") (pintype "passive"))
      (node (ref "JX2") (pin "51") (pinfunction "51_51") (pintype "passive"))
      (node (ref "JX2") (pin "52") (pinfunction "52_52") (pintype "passive"))
      (node (ref "JX2") (pin "65") (pinfunction "65_65") (pintype "passive"))
      (node (ref "JX2") (pin "66") (pinfunction "66_66") (pintype "passive"))
      (node (ref "JX2") (pin "71") (pinfunction "71_71") (pintype "passive"))
      (node (ref "JX2") (pin "72") (pinfunction "72_72") (pintype "passive"))
      (node (ref "JX2") (pin "77") (pinfunction "77_77") (pintype "passive"))
      (node (ref "JX2") (pin "85") (pinfunction "85_85") (pintype "passive"))
      (node (ref "JX2") (pin "86") (pinfunction "86_86") (pintype "passive"))
      (node (ref "JX2") (pin "91") (pinfunction "91_91") (pintype "passive"))
      (node (ref "JX2") (pin "92") (pinfunction "92_92") (pintype "passive"))
      (node (ref "P1") (pin "5") (pinfunction "5_5") (pintype "passive"))
    )
    (net (code "135") (name "VBATT") (class "Default")
      (node (ref "P1") (pin "1") (pinfunction "1_1") (pintype "passive"))
    )
    (net (code "136") (name "VCC") (class "Default")
      (node (ref "C1") (pin "2") (pinfunction "2_2") (pintype "passive"))
      (node (ref "C3") (pin "2") (pinfunction "2_2") (pintype "passive"))
      (node (ref "C5") (pin "2") (pinfunction "2_2") (pintype "passive"))
      (node (ref "C7") (pin "2") (pinfunction "2_2") (pintype "passive"))
      (node (ref "CON5") (pin "29") (pinfunction "29_29") (pintype "passive"))
      (node (ref "CON5") (pin "30") (pinfunction "30_30") (pintype "passive"))
      (node (ref "CON6") (pin "29") (pinfunction "29_29") (pintype "passive"))
      (node (ref "CON6") (pin "30") (pinfunction "30_30") (pintype "passive"))
      (node (ref "JX1") (pin "57") (pinfunction "57_57") (pintype "passive"))
      (node (ref "JX1") (pin "58") (pinfunction "58_58") (pintype "passive"))
      (node (ref "JX1") (pin "59") (pinfunction "59_59") (pintype "passive"))
      (node (ref "JX1") (pin "60") (pinfunction "60_60") (pintype "passive"))
      (node (ref "JX2") (pin "12") (pinfunction "12_12") (pintype "passive"))
      (node (ref "JX2") (pin "57") (pinfunction "57_57") (pintype "passive"))
      (node (ref "JX2") (pin "58") (pinfunction "58_58") (pintype "passive"))
      (node (ref "JX2") (pin "59") (pinfunction "59_59") (pintype "passive"))
      (node (ref "JX2") (pin "60") (pinfunction "60_60") (pintype "passive"))
      (node (ref "P1") (pin "2") (pinfunction "2_2") (pintype "passive"))
    )
    (net (code "137") (name "VCCIO") (class "Default")
      (node (ref "C2") (pin "2") (pinfunction "2_2") (pintype "passive"))
      (node (ref "C4") (pin "2") (pinfunction "2_2") (pintype "passive"))
      (node (ref "C6") (pin "2") (pinfunction "2_2") (pintype "passive"))
      (node (ref "C8") (pin "2") (pinfunction "2_2") (pintype "passive"))
      (node (ref "CON1") (pin "4") (pinfunction "4_4") (pintype "passive"))
      (node (ref "CON2") (pin "4") (pinfunction "4_4") (pintype "passive"))
      (node (ref "CON3") (pin "12") (pinfunction "12_12") (pintype "passive"))
      (node (ref "CON3") (pin "6") (pinfunction "6_6") (pintype "passive"))
      (node (ref "CON5") (pin "57") (pinfunction "57_57") (pintype "passive"))
      (node (ref "CON5") (pin "58") (pinfunction "58_58") (pintype "passive"))
      (node (ref "CON6") (pin "57") (pinfunction "57_57") (pintype "passive"))
      (node (ref "CON6") (pin "58") (pinfunction "58_58") (pintype "passive"))
      (node (ref "JX1") (pin "78") (pinfunction "78_78") (pintype "passive"))
      (node (ref "JX1") (pin "79") (pinfunction "79_79") (pintype "passive"))
      (node (ref "JX1") (pin "80") (pinfunction "80_80") (pintype "passive"))
      (node (ref "JX2") (pin "78") (pinfunction "78_78") (pintype "passive"))
      (node (ref "JX2") (pin "79") (pinfunction "79_79") (pintype "passive"))
      (node (ref "JX2") (pin "80") (pinfunction "80_80") (pintype "passive"))
      (node (ref "JX2") (pin "98") (pinfunction "98_98") (pintype "passive"))
      (node (ref "P1") (pin "3") (pinfunction "3_3") (pintype "passive"))
    )
    (net (code "138") (name "unconnected-(CON3-Pad10)") (class "Default")
      (node (ref "CON3") (pin "10") (pinfunction "10_10") (pintype "passive+no_connect"))
    )
    (net (code "139") (name "unconnected-(JX1-Pad1)") (class "Default")
      (node (ref "JX1") (pin "1") (pinfunction "1_1") (pintype "passive+no_connect"))
    )
    (net (code "140") (name "unconnected-(JX1-Pad2)") (class "Default")
      (node (ref "JX1") (pin "2") (pinfunction "2_2") (pintype "passive+no_connect"))
    )
    (net (code "141") (name "unconnected-(JX1-Pad3)") (class "Default")
      (node (ref "JX1") (pin "3") (pinfunction "3_3") (pintype "passive+no_connect"))
    )
    (net (code "142") (name "unconnected-(JX1-Pad4)") (class "Default")
      (node (ref "JX1") (pin "4") (pinfunction "4_4") (pintype "passive+no_connect"))
    )
    (net (code "143") (name "unconnected-(JX1-Pad6)") (class "Default")
      (node (ref "JX1") (pin "6") (pinfunction "6_6") (pintype "passive+no_connect"))
    )
    (net (code "144") (name "unconnected-(JX1-Pad7)") (class "Default")
      (node (ref "JX1") (pin "7") (pinfunction "7_7") (pintype "passive+no_connect"))
    )
    (net (code "145") (name "unconnected-(JX1-Pad8)") (class "Default")
      (node (ref "JX1") (pin "8") (pinfunction "8_8") (pintype "passive+no_connect"))
    )
    (net (code "146") (name "unconnected-(JX2-Pad1)") (class "Default")
      (node (ref "JX2") (pin "1") (pinfunction "1_1") (pintype "passive+no_connect"))
    )
    (net (code "147") (name "unconnected-(JX2-Pad2)") (class "Default")
      (node (ref "JX2") (pin "2") (pinfunction "2_2") (pintype "passive+no_connect"))
    )
    (net (code "148") (name "unconnected-(JX2-Pad3)") (class "Default")
      (node (ref "JX2") (pin "3") (pinfunction "3_3") (pintype "passive+no_connect"))
    )
    (net (code "149") (name "unconnected-(JX2-Pad4)") (class "Default")
      (node (ref "JX2") (pin "4") (pinfunction "4_4") (pintype "passive+no_connect"))
    )
    (net (code "150") (name "unconnected-(JX2-Pad5)") (class "Default")
      (node (ref "JX2") (pin "5") (pinfunction "5_5") (pintype "passive+no_connect"))
    )
    (net (code "151") (name "unconnected-(JX2-Pad6)") (class "Default")
      (node (ref "JX2") (pin "6") (pinfunction "6_6") (pintype "passive+no_connect"))
    )
    (net (code "152") (name "unconnected-(JX2-Pad7)") (class "Default")
      (node (ref "JX2") (pin "7") (pinfunction "7_7") (pintype "passive+no_connect"))
    )
    (net (code "153") (name "unconnected-(JX2-Pad8)") (class "Default")
      (node (ref "JX2") (pin "8") (pinfunction "8_8") (pintype "passive+no_connect"))
    )
    (net (code "154") (name "unconnected-(JX2-Pad9)") (class "Default")
      (node (ref "JX2") (pin "9") (pinfunction "9_9") (pintype "passive+no_connect"))
    )
  )
)
